# cs301_group5_sensors.net
KiCad netlist of a schematic drawn in Altium Designer
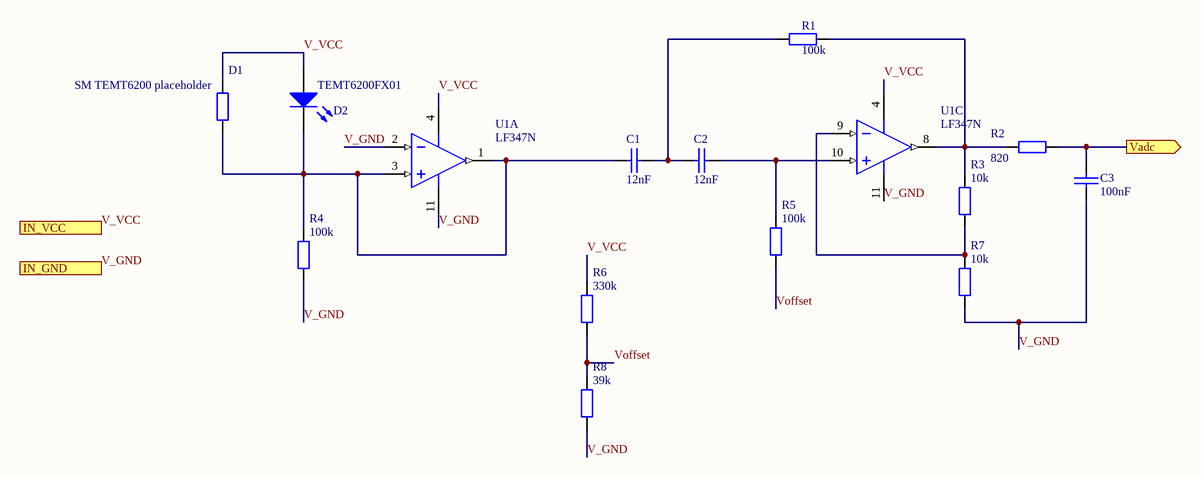
[diagram p0: cs301_group5_sensors.SchDoc]

(export (version "E")
  (design (tool "Eeschema 10.0.6"))
  (components
    (comp (ref "C1")
      (value "12nF")
      (footprint "CCAP-5P0")
      (description "SMT ceramic capacitor 0805 size")
      (libsource (lib "EE209_Library") (part "CerCap_TH_5P0"))
    )
    (comp (ref "C2")
      (value "12nF")
      (footprint "CCAP-5P0")
      (description "SMT ceramic capacitor 0805 size")
      (libsource (lib "EE209_Library") (part "CerCap_TH_5P0"))
    )
    (comp (ref "C3")
      (value "100nF")
      (footprint "CCAP-5P0")
      (description "SMT ceramic capacitor 0805 size")
      (libsource (lib "EE209_Library") (part "CerCap_TH_5P0"))
    )
    (comp (ref "D1")
      (value "SM TEMT6200 placeholder")
      (footprint "AXIAL-0.4")
      (fields (field (name "PUBLISHER") "Altium Limited"))
      (libsource (lib "") (part "Res_TH_0AX4_1"))
    )
    (comp (ref "D2")
      (value "TEMT6200FX01")
      (footprint "0805 LED")
      (description "SMT LED 0805 size")
      (fields
        (field (name "MANUFACTURER") "Lite-On Inc.")
        (field (name "MANUFACTURER PART NUMBER") "LTST-C170KGKT")
      )
      (libsource (lib "EE209_Library") (part "LED_SMT_0805"))
    )
    (comp (ref "R1")
      (value "100k")
      (footprint "AXIAL-0.4")
      (description "Through hole resistor")
      (fields (field (name "PUBLISHER") "Altium Limited"))
      (libsource (lib "") (part "Res_TH_0AX4_2"))
    )
    (comp (ref "R2")
      (value "820")
      (footprint "AXIAL-0.4")
      (description "Through hole resistor")
      (fields (field (name "PUBLISHER") "Altium Limited"))
      (libsource (lib "EE209_Library") (part "Res_TH_0AX4"))
    )
    (comp (ref "R3")
      (value "10k")
      (footprint "AXIAL-0.4")
      (description "Through hole resistor")
      (fields (field (name "PUBLISHER") "Altium Limited"))
      (libsource (lib "") (part "Res_TH_0AX4_1"))
    )
    (comp (ref "R4")
      (value "100k")
      (footprint "AXIAL-0.4")
      (description "Through hole resistor")
      (fields (field (name "PUBLISHER") "Altium Limited"))
      (libsource (lib "") (part "Res_TH_0AX4_1"))
    )
    (comp (ref "R5")
      (value "100k")
      (footprint "AXIAL-0.4")
      (description "Through hole resistor")
      (fields (field (name "PUBLISHER") "Altium Limited"))
      (libsource (lib "") (part "Res_TH_0AX4_1"))
    )
    (comp (ref "R6")
      (value "330k")
      (footprint "AXIAL-0.4")
      (description "Through hole resistor")
      (fields (field (name "PUBLISHER") "Altium Limited"))
      (libsource (lib "") (part "Res_TH_0AX4_1"))
    )
    (comp (ref "R7")
      (value "10k")
      (footprint "AXIAL-0.4")
      (description "Through hole resistor")
      (fields (field (name "PUBLISHER") "Altium Limited"))
      (libsource (lib "") (part "Res_TH_0AX4_1"))
    )
    (comp (ref "R8")
      (value "39k")
      (footprint "AXIAL-0.4")
      (description "Through hole resistor")
      (fields (field (name "PUBLISHER") "Altium Limited"))
      (libsource (lib "") (part "Res_TH_0AX4_1"))
    )
    (comp (ref "U1")
      (value "LF347N")
      (footprint "N0014A")
      (description "Wide Bandwidth Quad JFET Input Operational Amplifier, 14-pin MDIP")
      (fields (field (name "MANUFACTURER") "Texas Instruments"))
      (libsource (lib "Altium Content Vault") (part "AMP-OPA-LF147-14"))
    )
  )
  (nets
    (net (code "1") (name "/V_GND") (class "Default")
      (node (ref "C3") (pin "2") (pinfunction "2_2") (pintype "passive"))
      (node (ref "R4") (pin "1") (pinfunction "1_1") (pintype "passive"))
      (node (ref "R7") (pin "1") (pinfunction "1_1") (pintype "passive"))
      (node (ref "R8") (pin "1") (pinfunction "1_1") (pintype "passive"))
      (node (ref "U1") (pin "11") (pinfunction "V-_11") (pintype "power_in"))
      (node (ref "U1") (pin "2") (pinfunction "IN1-_2") (pintype "input"))
    )
    (net (code "2") (name "/V_VCC") (class "Default")
      (node (ref "D1") (pin "2") (pinfunction "2_2") (pintype "passive"))
      (node (ref "D2") (pin "1") (pinfunction "A_1") (pintype "passive"))
      (node (ref "R6") (pin "2") (pinfunction "2_2") (pintype "passive"))
      (node (ref "U1") (pin "4") (pinfunction "V+_4") (pintype "power_in"))
    )
    (net (code "3") (name "/Vadc") (class "Default")
      (node (ref "C3") (pin "1") (pinfunction "1_1") (pintype "passive"))
      (node (ref "R2") (pin "1") (pinfunction "1_1") (pintype "passive"))
    )
    (net (code "4") (name "/Voffset") (class "Default")
      (node (ref "R5") (pin "1") (pinfunction "1_1") (pintype "passive"))
      (node (ref "R6") (pin "1") (pinfunction "1_1") (pintype "passive"))
      (node (ref "R8") (pin "2") (pinfunction "2_2") (pintype "passive"))
    )
    (net (code "5") (name "Net-(C1-Pad2)") (class "Default")
      (node (ref "C1") (pin "2") (pinfunction "2_2") (pintype "passive"))
      (node (ref "C2") (pin "1") (pinfunction "1_1") (pintype "passive"))
      (node (ref "R1") (pin "1") (pinfunction "1_1") (pintype "passive"))
    )
    (net (code "6") (name "Net-(D2-K)") (class "Default")
      (node (ref "C1") (pin "1") (pinfunction "1_1") (pintype "passive"))
      (node (ref "D1") (pin "1") (pinfunction "1_1") (pintype "passive"))
      (node (ref "D2") (pin "2") (pinfunction "K_2") (pintype "passive"))
      (node (ref "R4") (pin "2") (pinfunction "2_2") (pintype "passive"))
      (node (ref "U1") (pin "1") (pinfunction "OUT1_1") (pintype "output"))
      (node (ref "U1") (pin "3") (pinfunction "IN1+_3") (pintype "input"))
    )
    (net (code "7") (name "Net-(U1C-IN3+)") (class "Default")
      (node (ref "C2") (pin "2") (pinfunction "2_2") (pintype "passive"))
      (node (ref "R5") (pin "2") (pinfunction "2_2") (pintype "passive"))
      (node (ref "U1") (pin "10") (pinfunction "IN3+_10") (pintype "input"))
    )
    (net (code "8") (name "Net-(U1C-IN3-)") (class "Default")
      (node (ref "R3") (pin "1") (pinfunction "1_1") (pintype "passive"))
      (node (ref "R7") (pin "2") (pinfunction "2_2") (pintype "passive"))
      (node (ref "U1") (pin "9") (pinfunction "IN3-_9") (pintype "input"))
    )
    (net (code "9") (name "Net-(U1C-OUT3)") (class "Default")
      (node (ref "R1") (pin "2") (pinfunction "2_2") (pintype "passive"))
      (node (ref "R2") (pin "2") (pinfunction "2_2") (pintype "passive"))
      (node (ref "R3") (pin "2") (pinfunction "2_2") (pintype "passive"))
      (node (ref "U1") (pin "8") (pinfunction "OUT3_8") (pintype "output"))
    )
  )
)
